# switchy_stamp_pth_mk1_buck.net
KiCad netlist of a schematic drawn in EAGLE
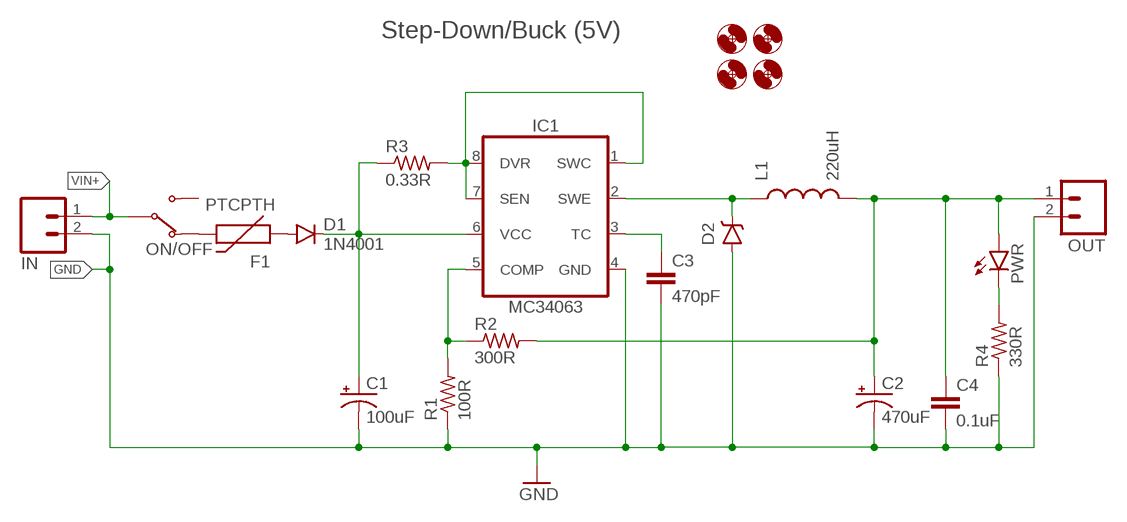
[diagram p0: schematic, sheet 1]

(export (version "E")
  (design (tool "Eeschema 10.0.6"))
  (components
    (comp (ref "C1")
      (value "100uF")
      (footprint "eagle-import:E2,5-7")
      (libsource (lib "eagle-import") (part "CAPACITOR-POLARIZEDE2.5-7"))
    )
    (comp (ref "C2")
      (value "470uF")
      (footprint "eagle-import:E2,5-7")
      (libsource (lib "eagle-import") (part "CAPACITOR-POLARIZEDE2.5-7"))
    )
    (comp (ref "C3")
      (value "470pF")
      (footprint "eagle-import:C025-024X044")
      (libsource (lib "eagle-import") (part "CAPACITOR-CERAMIC025-024X044"))
    )
    (comp (ref "C4")
      (value "0.1uF")
      (footprint "eagle-import:C025-024X044")
      (libsource (lib "eagle-import") (part "CAPACITOR-CERAMIC025-024X044"))
    )
    (comp (ref "D1")
      (value "1N4001")
      (footprint "eagle-import:DIODE-10.16MM")
      (libsource (lib "eagle-import") (part "DIODEPTH-10.68MM"))
    )
    (comp (ref "D2")
      (value "1N5819")
      (footprint "eagle-import:DIODE-10.16MM")
      (libsource (lib "eagle-import") (part "DIODE-SCHOTTKYPTH-10.16MM"))
    )
    (comp (ref "F1")
      (value "PTCPTH")
      (footprint "eagle-import:PTC")
      (libsource (lib "eagle-import") (part "PTCPTH"))
    )
    (comp (ref "H1")
      (value "HOLE#2")
      (footprint "eagle-import:HOLE-#2")
      (libsource (lib "eagle-import") (part "HOLE#2"))
    )
    (comp (ref "H2")
      (value "HOLE#2")
      (footprint "eagle-import:HOLE-#2")
      (libsource (lib "eagle-import") (part "HOLE#2"))
    )
    (comp (ref "H3")
      (value "HOLE#2")
      (footprint "eagle-import:HOLE-#2")
      (libsource (lib "eagle-import") (part "HOLE#2"))
    )
    (comp (ref "H4")
      (value "HOLE#2")
      (footprint "eagle-import:HOLE-#2")
      (libsource (lib "eagle-import") (part "HOLE#2"))
    )
    (comp (ref "IC1")
      (value "MC34063")
      (footprint "eagle-import:DIP-08")
      (libsource (lib "eagle-import") (part "MC34063DIP"))
    )
    (comp (ref "IN")
      (value "M02JST-PTH-2")
      (footprint "eagle-import:JST-2-PH-RA-PTH")
      (libsource (lib "eagle-import") (part "M02JST-PTH-2"))
    )
    (comp (ref "L1")
      (value "220uH")
      (footprint "eagle-import:RADIAL-PTH-6MMDIA")
      (libsource (lib "eagle-import") (part "INDUCTORPTH-RADIAL-6MMDIA"))
    )
    (comp (ref "ON/OFF")
      (value "SWITCH-SPDTSSA-12")
      (footprint "eagle-import:SWITCH-SPDT-SSA-12")
      (libsource (lib "eagle-import") (part "SWITCH-SPDTSSA-12"))
    )
    (comp (ref "OUT")
      (value "M02JST-PTH-2")
      (footprint "eagle-import:JST-2-PH-RA-PTH")
      (libsource (lib "eagle-import") (part "M02JST-PTH-2"))
    )
    (comp (ref "PWR")
      (value "LED3MM")
      (footprint "eagle-import:LED3MM")
      (libsource (lib "eagle-import") (part "LED3MM"))
    )
    (comp (ref "R1")
      (value "100R")
      (footprint "eagle-import:RESISTOR-AXIAL-PTH-5.08MM")
      (libsource (lib "eagle-import") (part "RESISTORPTH-AXIAL-5.08MM"))
    )
    (comp (ref "R2")
      (value "300R")
      (footprint "eagle-import:RESISTOR-AXIAL-PTH-5.08MM")
      (libsource (lib "eagle-import") (part "RESISTORPTH-AXIAL-5.08MM"))
    )
    (comp (ref "R3")
      (value "0.33R")
      (footprint "eagle-import:RESISTOR-AXIAL-PTH-10.16MM")
      (libsource (lib "eagle-import") (part "RESISTORPTH-AXIAL-10.16MM"))
    )
    (comp (ref "R4")
      (value "330R")
      (footprint "eagle-import:RESISTOR-AXIAL-PTH-5.08MM")
      (libsource (lib "eagle-import") (part "RESISTORPTH-AXIAL-5.08MM"))
    )
  )
  (nets
    (net (code "1") (name "GND") (class "Default")
      (node (ref "C1") (pin "-") (pinfunction "-_-") (pintype "passive"))
      (node (ref "C2") (pin "-") (pinfunction "-_-") (pintype "passive"))
      (node (ref "C3") (pin "2") (pinfunction "2_2") (pintype "passive"))
      (node (ref "C4") (pin "2") (pinfunction "2_2") (pintype "passive"))
      (node (ref "D2") (pin "A") (pinfunction "A_A") (pintype "passive"))
      (node (ref "IC1") (pin "4") (pinfunction "GND_4") (pintype "bidirectional"))
      (node (ref "IN") (pin "2") (pinfunction "2_2") (pintype "passive"))
      (node (ref "OUT") (pin "2") (pinfunction "2_2") (pintype "passive"))
      (node (ref "R1") (pin "P$1") (pinfunction "1_P$1") (pintype "passive"))
      (node (ref "R4") (pin "P$1") (pinfunction "1_P$1") (pintype "passive"))
    )
    (net (code "2") (name "Net-(F1-1)") (class "Default")
      (node (ref "D1") (pin "A") (pinfunction "A_A") (pintype "passive"))
      (node (ref "F1") (pin "P$1") (pinfunction "1_P$1") (pintype "bidirectional"))
    )
    (net (code "3") (name "Net-(F1-2)") (class "Default")
      (node (ref "F1") (pin "P$2") (pinfunction "2_P$2") (pintype "bidirectional"))
      (node (ref "ON/OFF") (pin "A") (pinfunction "NC_A") (pintype "passive"))
    )
    (net (code "4") (name "Net-(IC1-COMP)") (class "Default")
      (node (ref "IC1") (pin "5") (pinfunction "COMP_5") (pintype "bidirectional"))
      (node (ref "R1") (pin "P$2") (pinfunction "2_P$2") (pintype "passive"))
      (node (ref "R2") (pin "P$1") (pinfunction "1_P$1") (pintype "passive"))
    )
    (net (code "5") (name "Net-(IC1-DVR)") (class "Default")
      (node (ref "IC1") (pin "1") (pinfunction "SWC_1") (pintype "bidirectional"))
      (node (ref "IC1") (pin "7") (pinfunction "SEN_7") (pintype "bidirectional"))
      (node (ref "IC1") (pin "8") (pinfunction "DVR_8") (pintype "bidirectional"))
      (node (ref "R3") (pin "P$2") (pinfunction "2_P$2") (pintype "passive"))
    )
    (net (code "6") (name "Net-(IC1-SWE)") (class "Default")
      (node (ref "D2") (pin "C") (pinfunction "C_C") (pintype "passive"))
      (node (ref "IC1") (pin "2") (pinfunction "SWE_2") (pintype "bidirectional"))
      (node (ref "L1") (pin "1") (pinfunction "1_1") (pintype "passive"))
    )
    (net (code "7") (name "Net-(IC1-TC)") (class "Default")
      (node (ref "C3") (pin "1") (pinfunction "1_1") (pintype "passive"))
      (node (ref "IC1") (pin "3") (pinfunction "TC_3") (pintype "bidirectional"))
    )
    (net (code "8") (name "Net-(IC1-VCC)") (class "Default")
      (node (ref "C1") (pin "+") (pinfunction "+_+") (pintype "passive"))
      (node (ref "D1") (pin "C") (pinfunction "C_C") (pintype "passive"))
      (node (ref "IC1") (pin "6") (pinfunction "VCC_6") (pintype "bidirectional"))
      (node (ref "R3") (pin "P$1") (pinfunction "1_P$1") (pintype "passive"))
    )
    (net (code "9") (name "Net-(PWR-C)") (class "Default")
      (node (ref "PWR") (pin "K") (pinfunction "C_K") (pintype "passive"))
      (node (ref "R4") (pin "P$2") (pinfunction "2_P$2") (pintype "passive"))
    )
    (net (code "10") (name "Net-(R2-2)") (class "Default")
      (node (ref "C2") (pin "+") (pinfunction "+_+") (pintype "passive"))
      (node (ref "C4") (pin "1") (pinfunction "1_1") (pintype "passive"))
      (node (ref "L1") (pin "2") (pinfunction "2_2") (pintype "passive"))
      (node (ref "OUT") (pin "1") (pinfunction "1_1") (pintype "passive"))
      (node (ref "PWR") (pin "A") (pinfunction "A_A") (pintype "passive"))
      (node (ref "R2") (pin "P$2") (pinfunction "2_P$2") (pintype "passive"))
    )
    (net (code "11") (name "VIN+") (class "Default")
      (node (ref "IN") (pin "1") (pinfunction "1_1") (pintype "passive"))
      (node (ref "ON/OFF") (pin "COM") (pinfunction "COM_COM") (pintype "passive"))
    )
    (net (code "12") (name "unconnected-(ON/OFF-NO-PadB)") (class "Default")
      (node (ref "ON/OFF") (pin "B") (pinfunction "NO_B") (pintype "passive"))
    )
  )
)
